# 10_SDMMC.net
KiCad netlist of a schematic drawn in Altium Designer
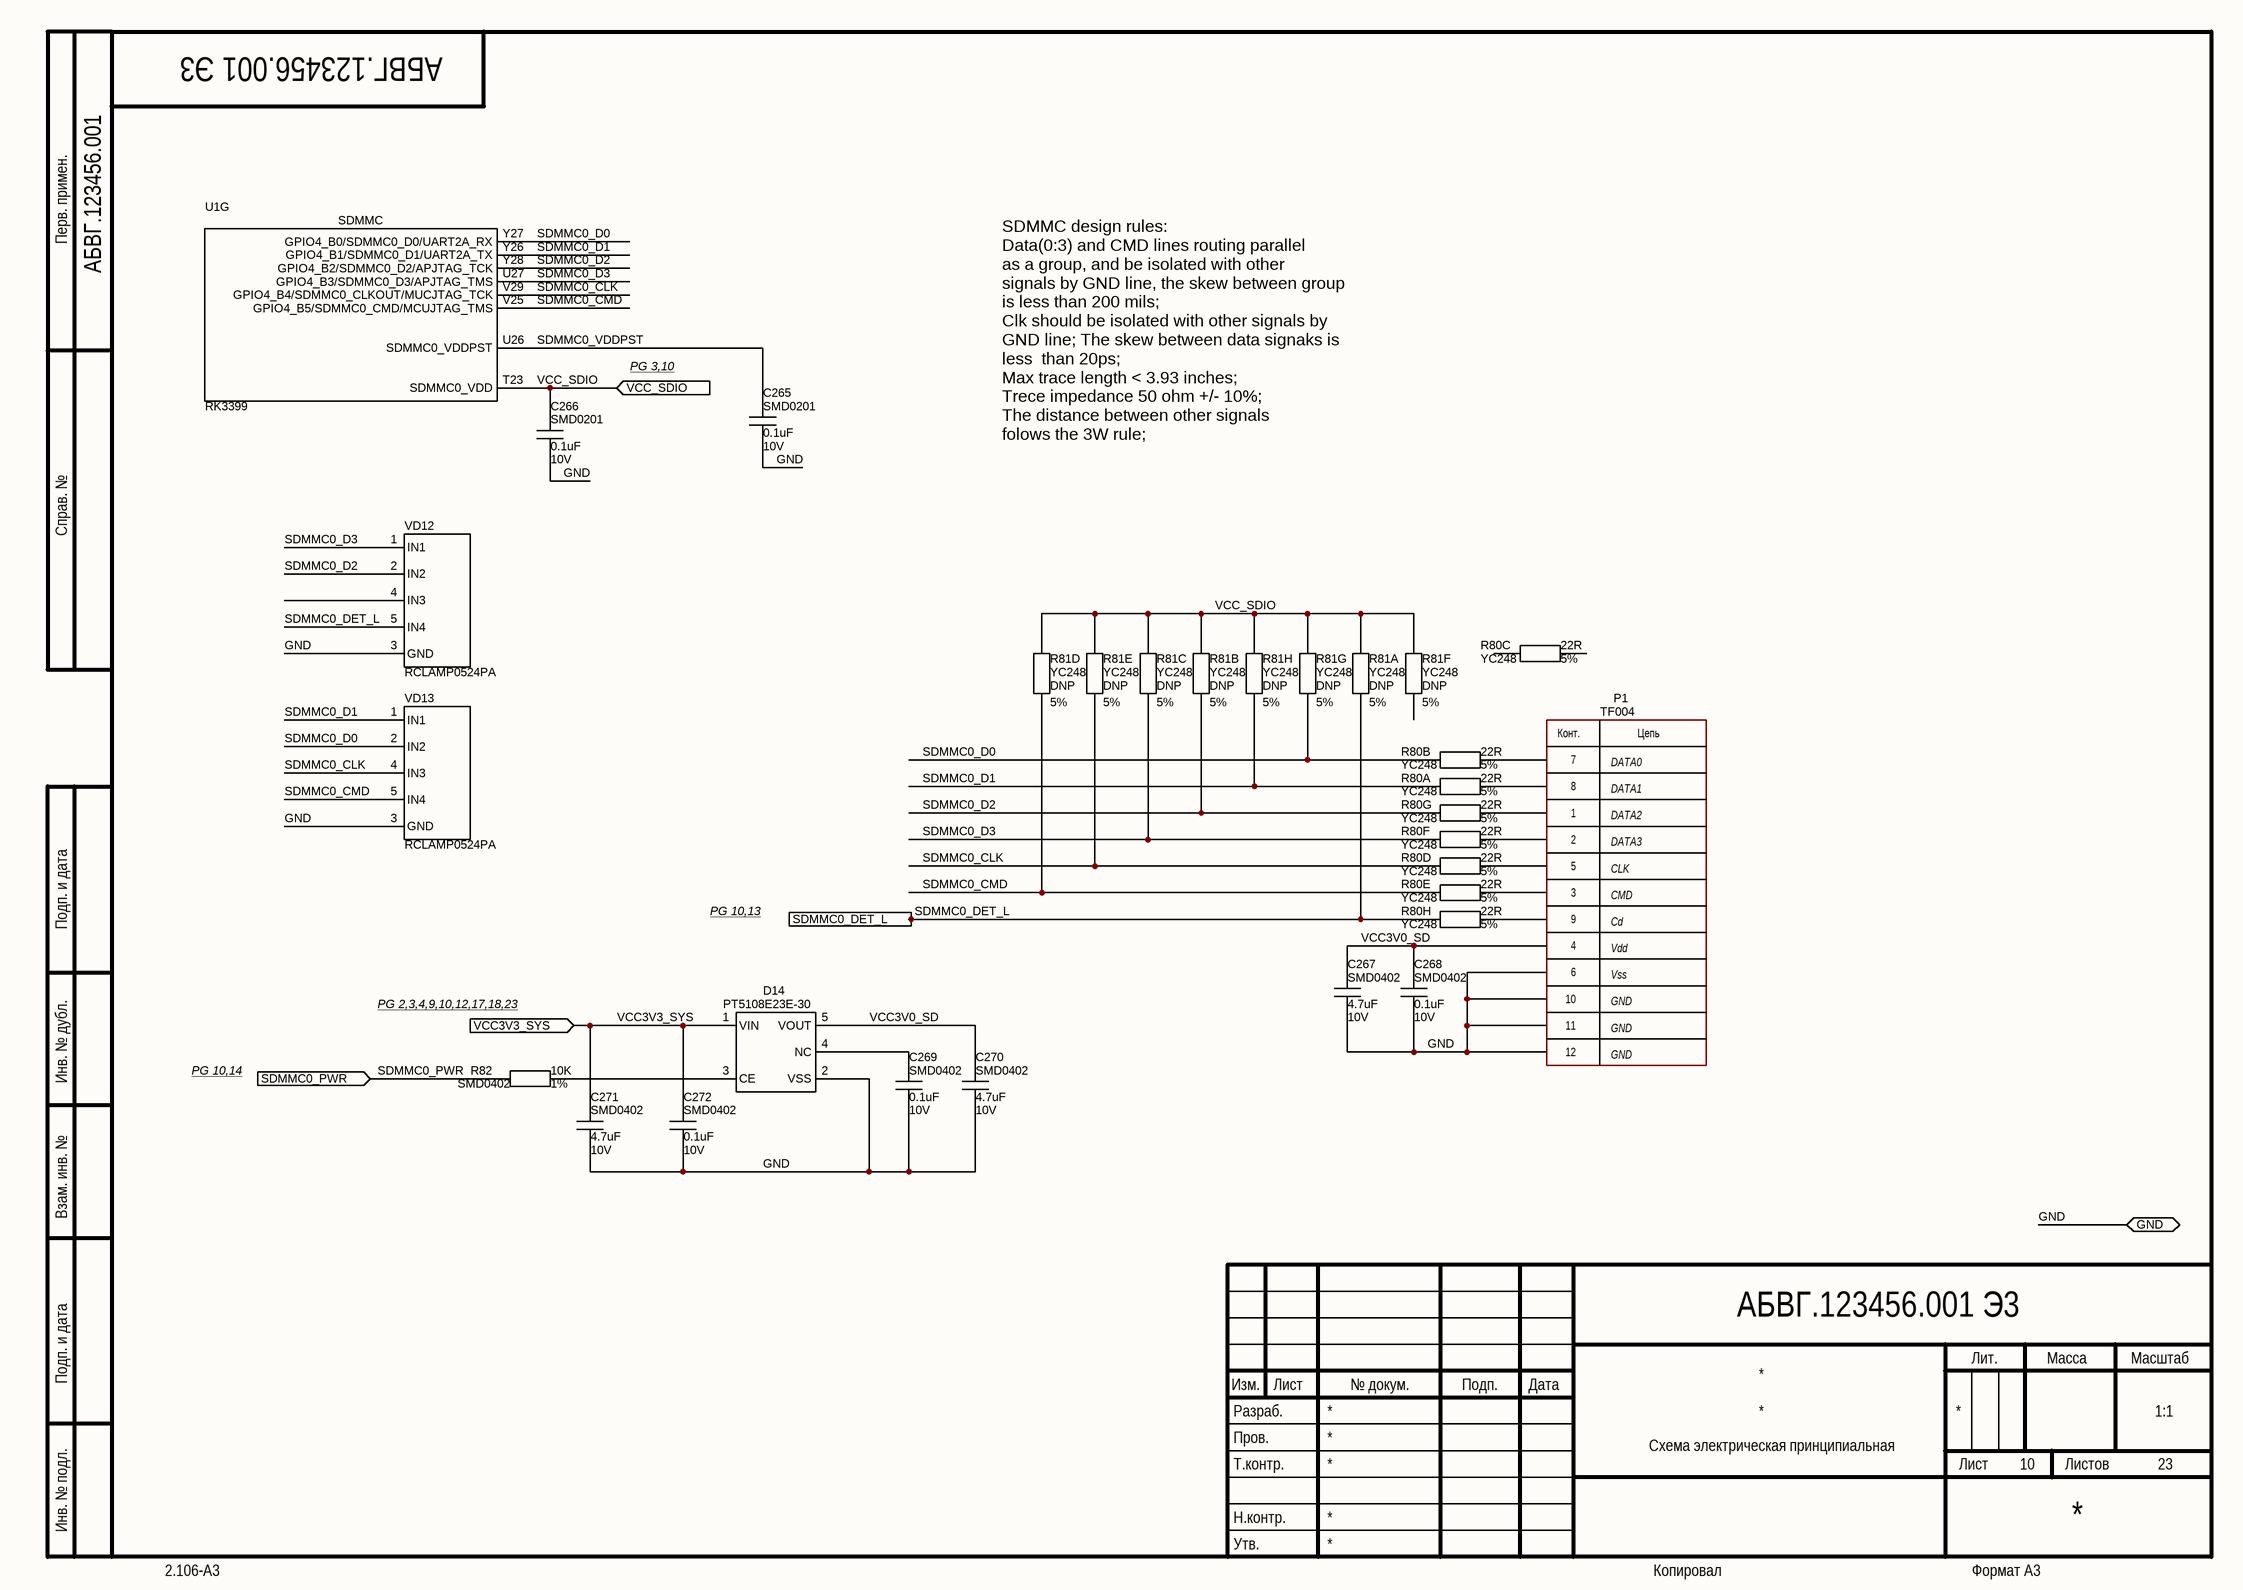
[diagram p0: 10 SDMMC.SchDoc]

(export (version "E")
  (design (tool "Eeschema 10.0.6"))
  (components
    (comp (ref "C265")
      (value "0.1uF")
      (footprint "Didur_PcbLib_1:CAP_SMD_0201")
      (fields
        (field (name "PACKAGE") "SMD0201")
        (field (name "PARTNUMBER") "CC0201KRX5R6BB104")
        (field (name "VOLTAGE") "10V")
      )
      (libsource (lib "Didur_SchLib_1") (part "Ceramic_Cap"))
    )
    (comp (ref "C266")
      (value "0.1uF")
      (footprint "Didur_PcbLib_1:CAP_SMD_0201")
      (fields
        (field (name "PACKAGE") "SMD0201")
        (field (name "PARTNUMBER") "CC0201KRX5R6BB104")
        (field (name "VOLTAGE") "10V")
      )
      (libsource (lib "Didur_SchLib_1") (part "Ceramic_Cap"))
    )
    (comp (ref "C267")
      (value "4.7uF")
      (footprint "Didur_PcbLib_1:CAP_SMD_0402")
      (fields
        (field (name "PACKAGE") "SMD0402")
        (field (name "PARTNUMBER") "CL05A475KP5NRNC")
        (field (name "VOLTAGE") "10V")
      )
      (libsource (lib "Didur_SchLib_1") (part "Ceramic_Cap"))
    )
    (comp (ref "C268")
      (value "0.1uF")
      (footprint "Didur_PcbLib_1:CAP_SMD_0402")
      (fields
        (field (name "PACKAGE") "SMD0402")
        (field (name "PARTNUMBER") "CC0402KRX5R6BB104")
        (field (name "VOLTAGE") "10V")
      )
      (libsource (lib "Didur_SchLib_1") (part "Ceramic_Cap"))
    )
    (comp (ref "C269")
      (value "0.1uF")
      (footprint "Didur_PcbLib_1:CAP_SMD_0402")
      (fields
        (field (name "PACKAGE") "SMD0402")
        (field (name "PARTNUMBER") "CC0402KRX5R6BB104")
        (field (name "VOLTAGE") "10V")
      )
      (libsource (lib "Didur_SchLib_1") (part "Ceramic_Cap"))
    )
    (comp (ref "C270")
      (value "4.7uF")
      (footprint "Didur_PcbLib_1:CAP_SMD_0402")
      (fields
        (field (name "PACKAGE") "SMD0402")
        (field (name "PARTNUMBER") "CL05A475KP5NRNC")
        (field (name "VOLTAGE") "10V")
      )
      (libsource (lib "Didur_SchLib_1") (part "Ceramic_Cap"))
    )
    (comp (ref "C271")
      (value "4.7uF")
      (footprint "Didur_PcbLib_1:CAP_SMD_0402")
      (fields
        (field (name "PACKAGE") "SMD0402")
        (field (name "PARTNUMBER") "CL05A475KP5NRNC")
        (field (name "VOLTAGE") "10V")
      )
      (libsource (lib "Didur_SchLib_1") (part "Ceramic_Cap"))
    )
    (comp (ref "C272")
      (value "0.1uF")
      (footprint "Didur_PcbLib_1:CAP_SMD_0402")
      (fields
        (field (name "PACKAGE") "SMD0402")
        (field (name "PARTNUMBER") "CC0402KRX5R6BB104")
        (field (name "VOLTAGE") "10V")
      )
      (libsource (lib "Didur_SchLib_1") (part "Ceramic_Cap"))
    )
    (comp (ref "D14")
      (value "PT5108E23E-30")
      (footprint "Didur_PcbLib_1:SOT23-5")
      (libsource (lib "Didur_SchLib_1") (part "PT5108E23E-30"))
    )
    (comp (ref "P1")
      (value "TF004")
      (footprint "Didur_PcbLib_1:TF004")
      (libsource (lib "Didur_SchLib_1") (part "MicroSD 9E"))
    )
    (comp (ref "R80")
      (value "22R")
      (footprint "Didur_PcbLib_1:YC248")
      (fields
        (field (name "PACKAGE") "YC248")
        (field (name "PARTNUMBER") "YC248-JR-0722RL")
        (field (name "TOLERANCE") "5%")
      )
      (libsource (lib "") (part "YC248_1"))
    )
    (comp (ref "R81")
      (value "DNP")
      (footprint "Didur_PcbLib_1:YC248")
      (fields
        (field (name "PACKAGE") "YC248")
        (field (name "PARTNUMBER") "Do Not Place")
        (field (name "TOLERANCE") "5%")
      )
      (libsource (lib "Didur_SchLib_1") (part "YC248"))
    )
    (comp (ref "R82")
      (value "10K")
      (footprint "Didur_PcbLib_1:RES_SMD_0402")
      (fields
        (field (name "PACKAGE") "SMD0402")
        (field (name "PARTNUMBER") "RC0402FR-0710KL")
        (field (name "TOLERANCE") "1%")
      )
      (libsource (lib "Didur_SchLib_1") (part "Chip_Res"))
    )
    (comp (ref "U1")
      (value "RK3399")
      (footprint "BGA828C65P31X31_2100X2100X161N")
      (fields (field (name "Comment") "RK3399_FF"))
      (libsource (lib "Didur_SchLib_1") (part "RK3399_FF"))
    )
    (comp (ref "VD12")
      (value "RCLAMP0524PA")
      (footprint "Didur_PcbLib_1:RCLAMP0524PA")
      (libsource (lib "Didur_SchLib_1") (part "RCLAMP0524PA"))
    )
    (comp (ref "VD13")
      (value "RCLAMP0524PA")
      (footprint "Didur_PcbLib_1:RCLAMP0524PA")
      (libsource (lib "Didur_SchLib_1") (part "RCLAMP0524PA"))
    )
  )
  (nets
    (net (code "1") (name "/GND") (class "Default")
      (node (ref "C265") (pin "2") (pinfunction "2_2") (pintype "power_in"))
      (node (ref "C266") (pin "2") (pinfunction "2_2") (pintype "power_in"))
      (node (ref "C267") (pin "1") (pinfunction "1_1") (pintype "power_in"))
      (node (ref "C268") (pin "2") (pinfunction "2_2") (pintype "power_in"))
      (node (ref "C269") (pin "2") (pinfunction "2_2") (pintype "power_in"))
      (node (ref "C270") (pin "1") (pinfunction "1_1") (pintype "power_in"))
      (node (ref "C271") (pin "1") (pinfunction "1_1") (pintype "power_in"))
      (node (ref "C272") (pin "2") (pinfunction "2_2") (pintype "power_in"))
      (node (ref "D14") (pin "2") (pinfunction "VSS_2") (pintype "passive"))
      (node (ref "P1") (pin "10") (pinfunction "10_10") (pintype "power_in"))
      (node (ref "P1") (pin "11") (pinfunction "11_11") (pintype "power_in"))
      (node (ref "P1") (pin "12") (pinfunction "12_12") (pintype "power_in"))
      (node (ref "P1") (pin "6") (pinfunction "6_6") (pintype "power_in"))
      (node (ref "VD12") (pin "3") (pinfunction "GND_3") (pintype "passive"))
      (node (ref "VD13") (pin "3") (pinfunction "GND_3") (pintype "passive"))
    )
    (net (code "2") (name "/SDMMC0_CLK") (class "Default")
      (node (ref "R80") (pin "13") (pinfunction "13_13") (pintype "passive"))
      (node (ref "R81") (pin "12") (pinfunction "12_12") (pintype "passive"))
      (node (ref "U1") (pin "V29") (pinfunction "GPIO4_B4/SDMMC0_CLKOUT/MUCJTAG_TCK_V29") (pintype "passive"))
      (node (ref "VD13") (pin "4") (pinfunction "IN3_4") (pintype "passive"))
    )
    (net (code "3") (name "/SDMMC0_CMD") (class "Default")
      (node (ref "R80") (pin "12") (pinfunction "12_12") (pintype "passive"))
      (node (ref "R81") (pin "13") (pinfunction "13_13") (pintype "passive"))
      (node (ref "U1") (pin "V25") (pinfunction "GPIO4_B5/SDMMC0_CMD/MCUJTAG_TMS_V25") (pintype "passive"))
      (node (ref "VD13") (pin "5") (pinfunction "IN4_5") (pintype "passive"))
    )
    (net (code "4") (name "/SDMMC0_D0") (class "Default")
      (node (ref "R80") (pin "15") (pinfunction "15_15") (pintype "passive"))
      (node (ref "R81") (pin "10") (pinfunction "10_10") (pintype "passive"))
      (node (ref "U1") (pin "Y27") (pinfunction "GPIO4_B0/SDMMC0_D0/UART2A_RX_Y27") (pintype "passive"))
      (node (ref "VD13") (pin "2") (pinfunction "IN2_2") (pintype "passive"))
    )
    (net (code "5") (name "/SDMMC0_D1") (class "Default")
      (node (ref "R80") (pin "16") (pinfunction "16_16") (pintype "passive"))
      (node (ref "R81") (pin "9") (pinfunction "9_9") (pintype "passive"))
      (node (ref "U1") (pin "Y26") (pinfunction "GPIO4_B1/SDMMC0_D1/UART2A_TX_Y26") (pintype "passive"))
      (node (ref "VD13") (pin "1") (pinfunction "IN1_1") (pintype "passive"))
    )
    (net (code "6") (name "/SDMMC0_D2") (class "Default")
      (node (ref "R80") (pin "10") (pinfunction "10_10") (pintype "passive"))
      (node (ref "R81") (pin "15") (pinfunction "15_15") (pintype "passive"))
      (node (ref "U1") (pin "Y28") (pinfunction "GPIO4_B2/SDMMC0_D2/APJTAG_TCK_Y28") (pintype "passive"))
      (node (ref "VD12") (pin "2") (pinfunction "IN2_2") (pintype "passive"))
    )
    (net (code "7") (name "/SDMMC0_D3") (class "Default")
      (node (ref "R80") (pin "11") (pinfunction "11_11") (pintype "passive"))
      (node (ref "R81") (pin "14") (pinfunction "14_14") (pintype "passive"))
      (node (ref "U1") (pin "U27") (pinfunction "GPIO4_B3/SDMMC0_D3/APJTAG_TMS_U27") (pintype "passive"))
      (node (ref "VD12") (pin "1") (pinfunction "IN1_1") (pintype "passive"))
    )
    (net (code "8") (name "/SDMMC0_DET_L") (class "Default")
      (node (ref "R80") (pin "9") (pinfunction "9_9") (pintype "passive"))
      (node (ref "R81") (pin "16") (pinfunction "16_16") (pintype "passive"))
      (node (ref "VD12") (pin "5") (pinfunction "IN4_5") (pintype "passive"))
    )
    (net (code "9") (name "/SDMMC0_PWR") (class "Default")
      (node (ref "R82") (pin "2") (pinfunction "2_2") (pintype "passive"))
    )
    (net (code "10") (name "/SDMMC0_VDDPST") (class "Default")
      (node (ref "C265") (pin "1") (pinfunction "1_1") (pintype "power_in"))
      (node (ref "U1") (pin "U26") (pinfunction "SDMMC0_VDDPST_U26") (pintype "passive"))
    )
    (net (code "11") (name "/VCC3V0_SD") (class "Default")
      (node (ref "C267") (pin "2") (pinfunction "2_2") (pintype "power_in"))
      (node (ref "C268") (pin "1") (pinfunction "1_1") (pintype "power_in"))
      (node (ref "C270") (pin "2") (pinfunction "2_2") (pintype "power_in"))
      (node (ref "D14") (pin "5") (pinfunction "VOUT_5") (pintype "passive"))
      (node (ref "P1") (pin "4") (pinfunction "4_4") (pintype "power_in"))
    )
    (net (code "12") (name "/VCC3V3_SYS") (class "Default")
      (node (ref "C271") (pin "2") (pinfunction "2_2") (pintype "power_in"))
      (node (ref "C272") (pin "1") (pinfunction "1_1") (pintype "power_in"))
      (node (ref "D14") (pin "1") (pinfunction "VIN_1") (pintype "passive"))
    )
    (net (code "13") (name "/VCC_SDIO") (class "Default")
      (node (ref "C266") (pin "1") (pinfunction "1_1") (pintype "power_in"))
      (node (ref "R81") (pin "1") (pinfunction "1_1") (pintype "passive"))
      (node (ref "R81") (pin "2") (pinfunction "2_2") (pintype "passive"))
      (node (ref "R81") (pin "3") (pinfunction "3_3") (pintype "passive"))
      (node (ref "R81") (pin "4") (pinfunction "4_4") (pintype "passive"))
      (node (ref "R81") (pin "5") (pinfunction "5_5") (pintype "passive"))
      (node (ref "R81") (pin "6") (pinfunction "6_6") (pintype "passive"))
      (node (ref "R81") (pin "7") (pinfunction "7_7") (pintype "passive"))
      (node (ref "R81") (pin "8") (pinfunction "8_8") (pintype "passive"))
      (node (ref "U1") (pin "T23") (pinfunction "SDMMC0_VDD_T23") (pintype "passive"))
    )
    (net (code "14") (name "Net-(D14-CE)") (class "Default")
      (node (ref "D14") (pin "3") (pinfunction "CE_3") (pintype "passive"))
      (node (ref "R82") (pin "1") (pinfunction "1_1") (pintype "passive"))
    )
    (net (code "15") (name "Net-(D14-NC)") (class "Default")
      (node (ref "C269") (pin "1") (pinfunction "1_1") (pintype "power_in"))
      (node (ref "D14") (pin "4") (pinfunction "NC_4") (pintype "passive"))
    )
    (net (code "16") (name "Net-(P1-Pad1)") (class "Default")
      (node (ref "P1") (pin "1") (pinfunction "1_1") (pintype "passive"))
      (node (ref "R80") (pin "7") (pinfunction "7_7") (pintype "passive"))
    )
    (net (code "17") (name "Net-(P1-Pad2)") (class "Default")
      (node (ref "P1") (pin "2") (pinfunction "2_2") (pintype "passive"))
      (node (ref "R80") (pin "6") (pinfunction "6_6") (pintype "passive"))
    )
    (net (code "18") (name "Net-(P1-Pad3)") (class "Default")
      (node (ref "P1") (pin "3") (pinfunction "3_3") (pintype "power_in"))
      (node (ref "R80") (pin "5") (pinfunction "5_5") (pintype "passive"))
    )
    (net (code "19") (name "Net-(P1-Pad5)") (class "Default")
      (node (ref "P1") (pin "5") (pinfunction "5_5") (pintype "power_in"))
      (node (ref "R80") (pin "4") (pinfunction "4_4") (pintype "passive"))
    )
    (net (code "20") (name "Net-(P1-Pad7)") (class "Default")
      (node (ref "P1") (pin "7") (pinfunction "7_7") (pintype "power_in"))
      (node (ref "R80") (pin "2") (pinfunction "2_2") (pintype "passive"))
    )
    (net (code "21") (name "Net-(P1-Pad8)") (class "Default")
      (node (ref "P1") (pin "8") (pinfunction "8_8") (pintype "power_in"))
      (node (ref "R80") (pin "1") (pinfunction "1_1") (pintype "passive"))
    )
    (net (code "22") (name "Net-(P1-Pad9)") (class "Default")
      (node (ref "P1") (pin "9") (pinfunction "9_9") (pintype "power_in"))
      (node (ref "R80") (pin "8") (pinfunction "8_8") (pintype "passive"))
    )
    (net (code "23") (name "unconnected-(R80-Pad3)") (class "Default")
      (node (ref "R80") (pin "3") (pinfunction "3_3") (pintype "passive"))
    )
    (net (code "24") (name "unconnected-(R80-Pad14)") (class "Default")
      (node (ref "R80") (pin "14") (pinfunction "14_14") (pintype "passive"))
    )
    (net (code "25") (name "unconnected-(R81-Pad11)") (class "Default")
      (node (ref "R81") (pin "11") (pinfunction "11_11") (pintype "passive"))
    )
    (net (code "26") (name "unconnected-(VD12-IN3-Pad4)") (class "Default")
      (node (ref "VD12") (pin "4") (pinfunction "IN3_4") (pintype "passive"))
    )
  )
)
